# Adafruit_MacroPad_2040_rev_D.net
KiCad netlist of a schematic drawn in EAGLE
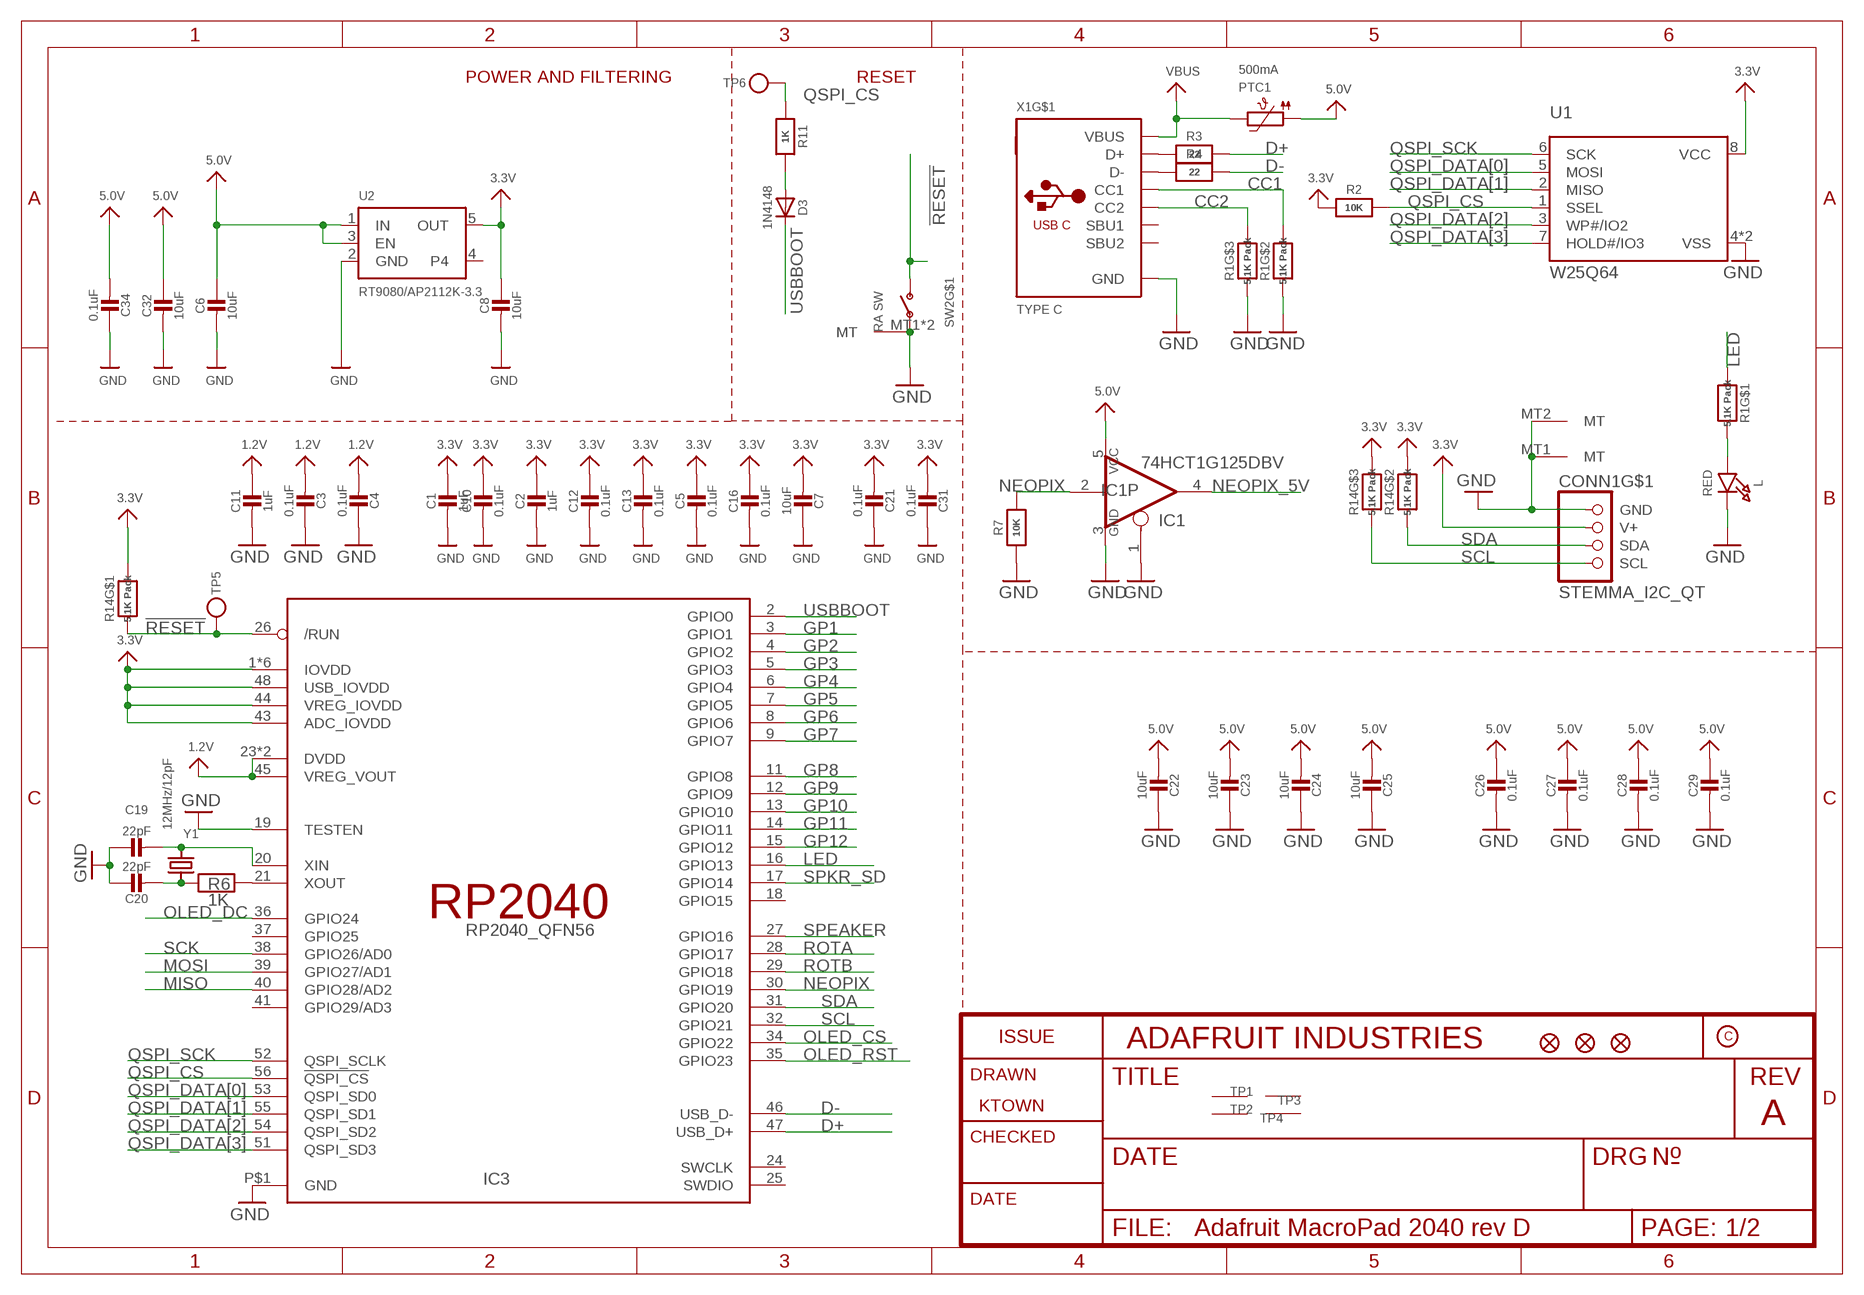
[diagram p0: schematic, sheet 1]
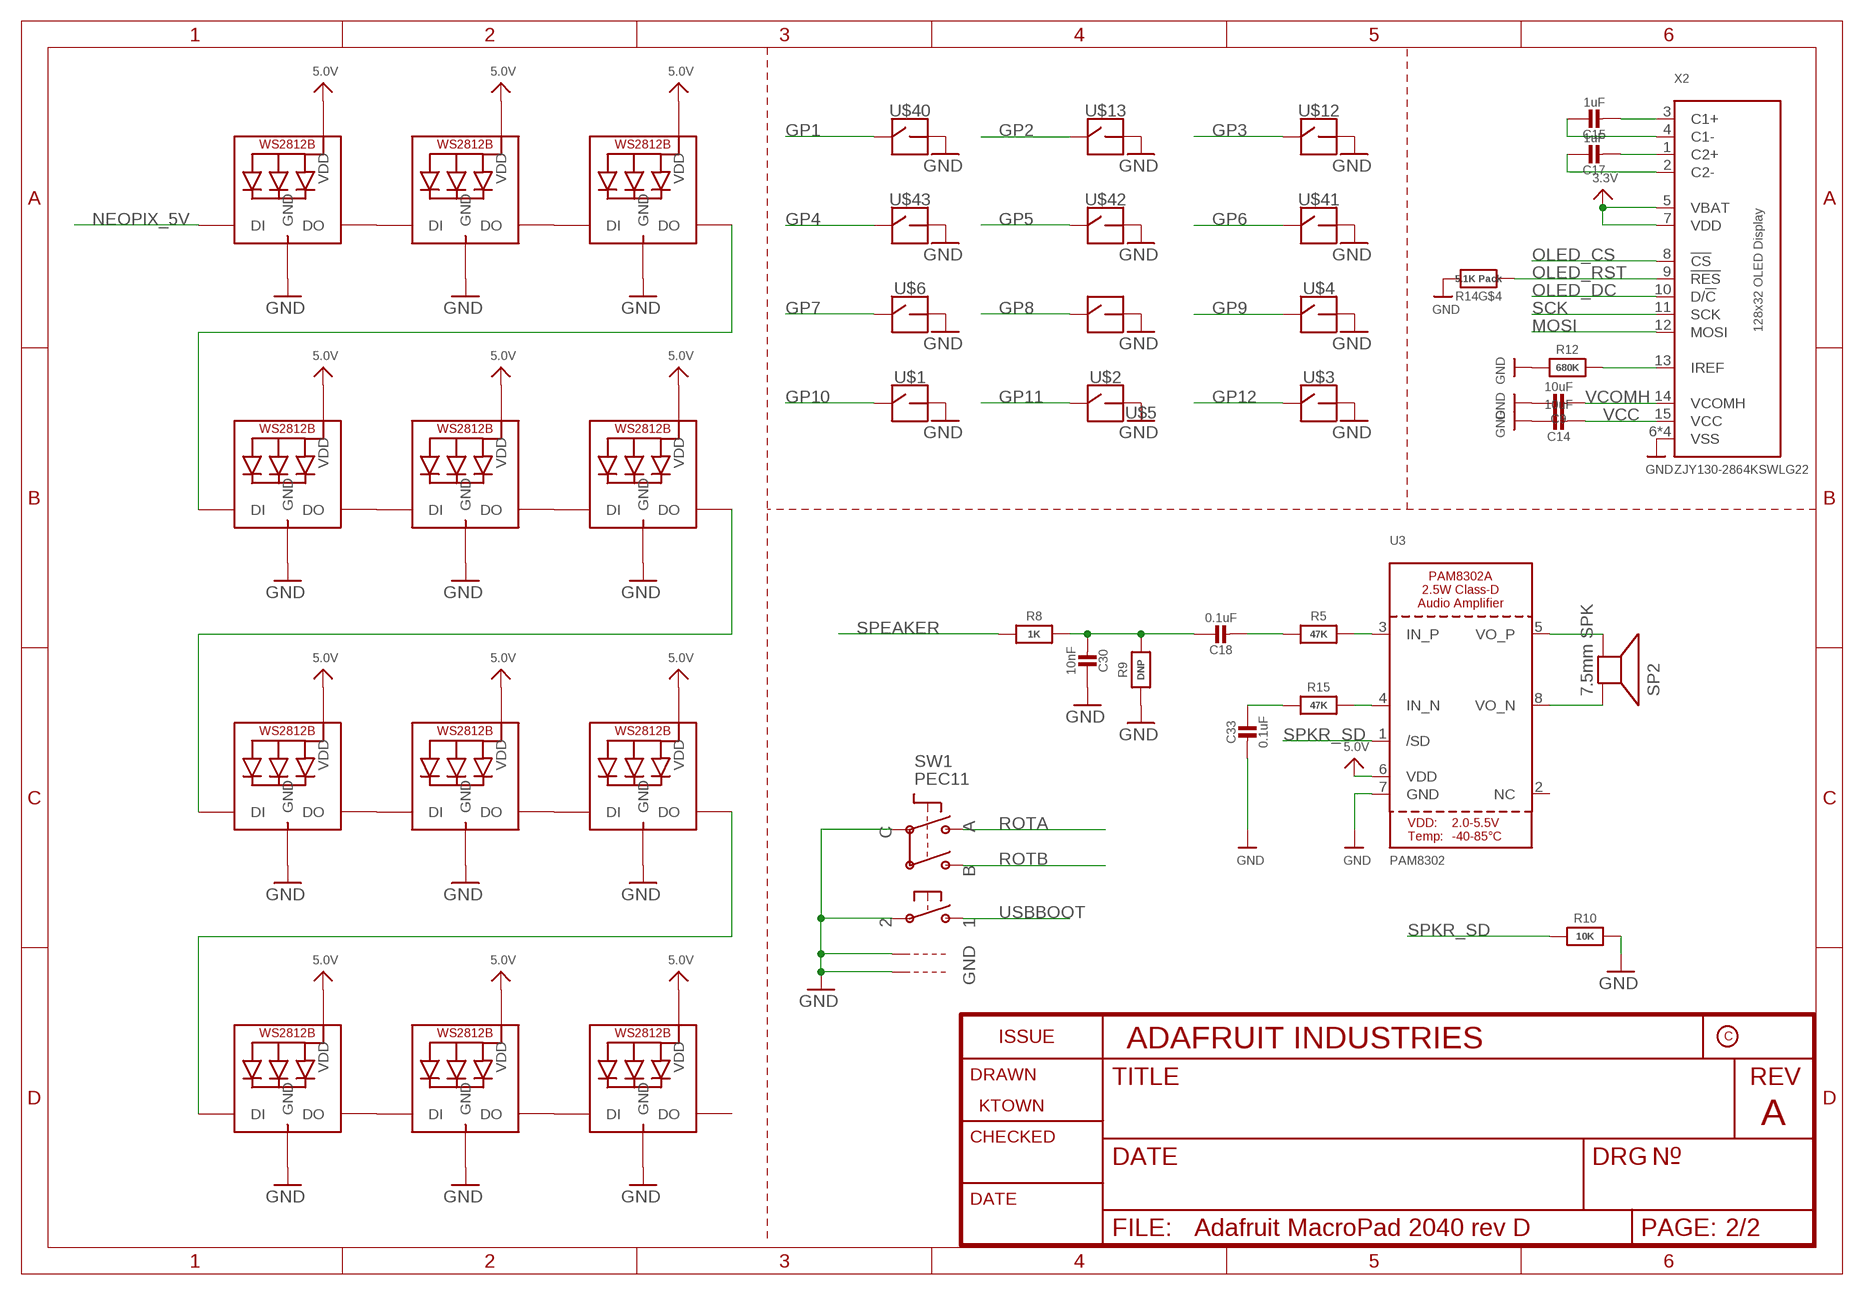
[diagram p1: schematic, sheet 2]

(export (version "E")
  (design (tool "Eeschema 10.0.6"))
  (components
    (comp (ref "C1")
      (value "1uF")
      (footprint "eagle-import:0603-NO")
      (libsource (lib "eagle-import") (part "CAP_CERAMIC0603_NO"))
    )
    (comp (ref "C2")
      (value "1uF")
      (footprint "eagle-import:0603-NO")
      (libsource (lib "eagle-import") (part "CAP_CERAMIC0603_NO"))
    )
    (comp (ref "C3")
      (value "0.1uF")
      (footprint "eagle-import:0603-NO")
      (libsource (lib "eagle-import") (part "CAP_CERAMIC0603_NO"))
    )
    (comp (ref "C4")
      (value "0.1uF")
      (footprint "eagle-import:0603-NO")
      (libsource (lib "eagle-import") (part "CAP_CERAMIC0603_NO"))
    )
    (comp (ref "C5")
      (value "0.1uF")
      (footprint "eagle-import:0603-NO")
      (libsource (lib "eagle-import") (part "CAP_CERAMIC0603_NO"))
    )
    (comp (ref "C6")
      (value "10uF")
      (footprint "eagle-import:0805-NO")
      (libsource (lib "eagle-import") (part "CAP_CERAMIC0805-NOOUTLINE"))
    )
    (comp (ref "C7")
      (value "10uF")
      (footprint "eagle-import:0805-NO")
      (libsource (lib "eagle-import") (part "CAP_CERAMIC0805-NOOUTLINE"))
    )
    (comp (ref "C8")
      (value "10uF")
      (footprint "eagle-import:0805-NO")
      (fields (field (name "REV") "D"))
      (libsource (lib "eagle-import") (part "CAP_CERAMIC0805-NOOUTLINE"))
    )
    (comp (ref "C10")
      (value "0.1uF")
      (footprint "eagle-import:0603-NO")
      (libsource (lib "eagle-import") (part "CAP_CERAMIC0603_NO"))
    )
    (comp (ref "C11")
      (value "1uF")
      (footprint "eagle-import:0603-NO")
      (libsource (lib "eagle-import") (part "CAP_CERAMIC0603_NO"))
    )
    (comp (ref "C12")
      (value "0.1uF")
      (footprint "eagle-import:0603-NO")
      (libsource (lib "eagle-import") (part "CAP_CERAMIC0603_NO"))
    )
    (comp (ref "C13")
      (value "0.1uF")
      (footprint "eagle-import:0603-NO")
      (libsource (lib "eagle-import") (part "CAP_CERAMIC0603_NO"))
    )
    (comp (ref "C16")
      (value "0.1uF")
      (footprint "eagle-import:0603-NO")
      (libsource (lib "eagle-import") (part "CAP_CERAMIC0603_NO"))
    )
    (comp (ref "C19")
      (value "22pF")
      (footprint "eagle-import:0603-NO")
      (libsource (lib "eagle-import") (part "CAP_CERAMIC0603_NO"))
    )
    (comp (ref "C20")
      (value "22pF")
      (footprint "eagle-import:0603-NO")
      (libsource (lib "eagle-import") (part "CAP_CERAMIC0603_NO"))
    )
    (comp (ref "C21")
      (value "0.1uF")
      (footprint "eagle-import:0603-NO")
      (libsource (lib "eagle-import") (part "CAP_CERAMIC0603_NO"))
    )
    (comp (ref "C22")
      (value "10uF")
      (footprint "eagle-import:0805-NO")
      (libsource (lib "eagle-import") (part "CAP_CERAMIC0805-NOOUTLINE"))
    )
    (comp (ref "C23")
      (value "10uF")
      (footprint "eagle-import:0805-NO")
      (libsource (lib "eagle-import") (part "CAP_CERAMIC0805-NOOUTLINE"))
    )
    (comp (ref "C24")
      (value "10uF")
      (footprint "eagle-import:0805-NO")
      (libsource (lib "eagle-import") (part "CAP_CERAMIC0805-NOOUTLINE"))
    )
    (comp (ref "C25")
      (value "10uF")
      (footprint "eagle-import:0805-NO")
      (libsource (lib "eagle-import") (part "CAP_CERAMIC0805-NOOUTLINE"))
    )
    (comp (ref "C26")
      (value "0.1uF")
      (footprint "eagle-import:0603-NO")
      (libsource (lib "eagle-import") (part "CAP_CERAMIC0603_NO"))
    )
    (comp (ref "C27")
      (value "0.1uF")
      (footprint "eagle-import:0603-NO")
      (libsource (lib "eagle-import") (part "CAP_CERAMIC0603_NO"))
    )
    (comp (ref "C28")
      (value "0.1uF")
      (footprint "eagle-import:0603-NO")
      (libsource (lib "eagle-import") (part "CAP_CERAMIC0603_NO"))
    )
    (comp (ref "C29")
      (value "0.1uF")
      (footprint "eagle-import:0603-NO")
      (libsource (lib "eagle-import") (part "CAP_CERAMIC0603_NO"))
    )
    (comp (ref "C31")
      (value "0.1uF")
      (footprint "eagle-import:0603-NO")
      (libsource (lib "eagle-import") (part "CAP_CERAMIC0603_NO"))
    )
    (comp (ref "C32")
      (value "10uF")
      (footprint "eagle-import:0805-NO")
      (libsource (lib "eagle-import") (part "CAP_CERAMIC0805-NOOUTLINE"))
    )
    (comp (ref "C34")
      (value "0.1uF")
      (footprint "eagle-import:0603-NO")
      (libsource (lib "eagle-import") (part "CAP_CERAMIC0603_NO"))
    )
    (comp (ref "CONN1")
      (value "STEMMA_I2C_QT")
      (footprint "eagle-import:JST_SH4")
      (libsource (lib "eagle-import") (part "STEMMA_I2C_QT"))
    )
    (comp (ref "D3")
      (value "1N4148")
      (footprint "eagle-import:SOD-323")
      (libsource (lib "eagle-import") (part "DIODESOD-323"))
    )
    (comp (ref "IC1")
      (value "74HCT1G125DBV")
      (footprint "eagle-import:SOT23-5")
      (libsource (lib "eagle-import") (part "741G125DBVAHC"))
    )
    (comp (ref "IC3")
      (value "RP2040_QFN56")
      (footprint "eagle-import:QFN56_7MM_REDUCEDEPAD")
      (libsource (lib "eagle-import") (part "RP2040_QFN56"))
    )
    (comp (ref "L")
      (value "RED")
      (footprint "eagle-import:CHIPLED_0603_NOOUTLINE")
      (libsource (lib "eagle-import") (part "LED0603_NOOUTLINE"))
    )
    (comp (ref "PTC1")
      (value "500mA")
      (footprint "eagle-import:0805-NO")
      (libsource (lib "eagle-import") (part "PTC_0805"))
    )
    (comp (ref "R1")
      (value "5.1K Pack")
      (footprint "eagle-import:RESPACK_4X0603")
      (libsource (lib "eagle-import") (part "RESISTOR_4PACK"))
    )
    (comp (ref "R2")
      (value "10K")
      (footprint "eagle-import:0603-NO")
      (libsource (lib "eagle-import") (part "RESISTOR_0603_NOOUT"))
    )
    (comp (ref "R3")
      (value "22")
      (footprint "eagle-import:0603-NO")
      (libsource (lib "eagle-import") (part "RESISTOR_0603_NOOUT"))
    )
    (comp (ref "R4")
      (value "22")
      (footprint "eagle-import:0603-NO")
      (libsource (lib "eagle-import") (part "RESISTOR_0603_NOOUT"))
    )
    (comp (ref "R6")
      (value "1K")
      (footprint "eagle-import:0603-NO")
      (libsource (lib "eagle-import") (part "RESISTOR_0603_NOOUT"))
    )
    (comp (ref "R7")
      (value "10K")
      (footprint "eagle-import:0603-NO")
      (libsource (lib "eagle-import") (part "RESISTOR_0603_NOOUT"))
    )
    (comp (ref "R11")
      (value "1K")
      (footprint "eagle-import:0603-NO")
      (libsource (lib "eagle-import") (part "RESISTOR_0603_NOOUT"))
    )
    (comp (ref "R14")
      (value "5.1K Pack")
      (footprint "eagle-import:RESPACK_4X0603")
      (libsource (lib "eagle-import") (part "RESISTOR_4PACK"))
    )
    (comp (ref "SW2")
      (value "RA SW")
      (footprint "eagle-import:SPST_TACTILE_RA")
      (libsource (lib "eagle-import") (part "SWITCH_SPST_MNT_TACT_RA"))
    )
    (comp (ref "TP1")
      (value "SEWTAP_SMTNUTM3")
      (footprint "eagle-import:SMT_NUT_3MM")
      (libsource (lib "eagle-import") (part "SEWTAP_SMTNUTM3"))
    )
    (comp (ref "TP2")
      (value "SEWTAP_SMTNUTM3")
      (footprint "eagle-import:SMT_NUT_3MM")
      (libsource (lib "eagle-import") (part "SEWTAP_SMTNUTM3"))
    )
    (comp (ref "TP3")
      (value "SEWTAP_SMTNUTM3")
      (footprint "eagle-import:SMT_NUT_3MM")
      (libsource (lib "eagle-import") (part "SEWTAP_SMTNUTM3"))
    )
    (comp (ref "TP4")
      (value "SEWTAP_SMTNUTM3")
      (footprint "eagle-import:SMT_NUT_3MM")
      (libsource (lib "eagle-import") (part "SEWTAP_SMTNUTM3"))
    )
    (comp (ref "TP5")
      (value "TESTPOINTROUND1.5MMNO")
      (footprint "eagle-import:TESTPOINT_ROUND_1.5MM_NO")
      (libsource (lib "eagle-import") (part "TESTPOINTROUND1.5MMNO"))
    )
    (comp (ref "TP6")
      (value "TESTPOINTROUND1.5MMNO")
      (footprint "eagle-import:TESTPOINT_ROUND_1.5MM_NO")
      (libsource (lib "eagle-import") (part "TESTPOINTROUND1.5MMNO"))
    )
    (comp (ref "U$34")
      (value "FIDUCIAL_1MM")
      (footprint "eagle-import:FIDUCIAL_1MM")
      (libsource (lib "eagle-import") (part "FIDUCIAL_1MM"))
    )
    (comp (ref "U$35")
      (value "FIDUCIAL_1MM")
      (footprint "eagle-import:FIDUCIAL_1MM")
      (libsource (lib "eagle-import") (part "FIDUCIAL_1MM"))
    )
    (comp (ref "U$80")
      (value "FIDUCIAL_1MM")
      (footprint "eagle-import:FIDUCIAL_1MM")
      (libsource (lib "eagle-import") (part "FIDUCIAL_1MM"))
    )
    (comp (ref "U1")
      (value "W25Q64")
      (footprint "eagle-import:USON8_4X4")
      (libsource (lib "eagle-import") (part "SPIFLASH_8PIN_4X4"))
    )
    (comp (ref "U2")
      (value "RT9080/AP2112K-3.3")
      (footprint "eagle-import:SOT23-5")
      (fields (field (name "JLC_ROTATION") "0"))
      (libsource (lib "eagle-import") (part "VREG_SOT23-5"))
    )
    (comp (ref "X1")
      (value "TYPE C")
      (footprint "eagle-import:USB_C_CUSB31-CFM2AX-01-X")
      (libsource (lib "eagle-import") (part "USB_C"))
    )
    (comp (ref "Y1")
      (value "12MHz/12pF")
      (footprint "eagle-import:CRYSTAL_2.5X2")
      (libsource (lib "eagle-import") (part "CRYSTAL2.5X2.0"))
    )
    (comp (ref "C9")
      (value "10uF")
      (footprint "eagle-import:0805-NO")
      (libsource (lib "eagle-import") (part "CAP_CERAMIC0805-NOOUTLINE"))
    )
    (comp (ref "C14")
      (value "10uF")
      (footprint "eagle-import:0805-NO")
      (libsource (lib "eagle-import") (part "CAP_CERAMIC0805-NOOUTLINE"))
    )
    (comp (ref "C15")
      (value "1uF")
      (footprint "eagle-import:0603-NO")
      (libsource (lib "eagle-import") (part "CAP_CERAMIC0603_NO"))
    )
    (comp (ref "C17")
      (value "1uF")
      (footprint "eagle-import:0603-NO")
      (libsource (lib "eagle-import") (part "CAP_CERAMIC0603_NO"))
    )
    (comp (ref "C18")
      (value "0.1uF")
      (footprint "eagle-import:0603-NO")
      (libsource (lib "eagle-import") (part "CAP_CERAMIC0603_NO"))
    )
    (comp (ref "C30")
      (value "10nF")
      (footprint "eagle-import:0603-NO")
      (libsource (lib "eagle-import") (part "CAP_CERAMIC0603_NO"))
    )
    (comp (ref "C33")
      (value "0.1uF")
      (footprint "eagle-import:0603-NO")
      (libsource (lib "eagle-import") (part "CAP_CERAMIC0603_NO"))
    )
    (comp (ref "LED1")
      (value "WS2812B_SK6812E")
      (footprint "eagle-import:NEO3535_REVERSE")
      (libsource (lib "eagle-import") (part "WS2812B_SK6812E"))
    )
    (comp (ref "LED2")
      (value "WS2812B_SK6812E")
      (footprint "eagle-import:NEO3535_REVERSE")
      (libsource (lib "eagle-import") (part "WS2812B_SK6812E"))
    )
    (comp (ref "LED3")
      (value "WS2812B_SK6812E")
      (footprint "eagle-import:NEO3535_REVERSE")
      (libsource (lib "eagle-import") (part "WS2812B_SK6812E"))
    )
    (comp (ref "LED4")
      (value "WS2812B_SK6812E")
      (footprint "eagle-import:NEO3535_REVERSE")
      (libsource (lib "eagle-import") (part "WS2812B_SK6812E"))
    )
    (comp (ref "LED5")
      (value "WS2812B_SK6812E")
      (footprint "eagle-import:NEO3535_REVERSE")
      (libsource (lib "eagle-import") (part "WS2812B_SK6812E"))
    )
    (comp (ref "LED6")
      (value "WS2812B_SK6812E")
      (footprint "eagle-import:NEO3535_REVERSE")
      (libsource (lib "eagle-import") (part "WS2812B_SK6812E"))
    )
    (comp (ref "LED7")
      (value "WS2812B_SK6812E")
      (footprint "eagle-import:NEO3535_REVERSE")
      (libsource (lib "eagle-import") (part "WS2812B_SK6812E"))
    )
    (comp (ref "LED8")
      (value "WS2812B_SK6812E")
      (footprint "eagle-import:NEO3535_REVERSE")
      (libsource (lib "eagle-import") (part "WS2812B_SK6812E"))
    )
    (comp (ref "LED9")
      (value "WS2812B_SK6812E")
      (footprint "eagle-import:NEO3535_REVERSE")
      (libsource (lib "eagle-import") (part "WS2812B_SK6812E"))
    )
    (comp (ref "LED10")
      (value "WS2812B_SK6812E")
      (footprint "eagle-import:NEO3535_REVERSE")
      (libsource (lib "eagle-import") (part "WS2812B_SK6812E"))
    )
    (comp (ref "LED11")
      (value "WS2812B_SK6812E")
      (footprint "eagle-import:NEO3535_REVERSE")
      (libsource (lib "eagle-import") (part "WS2812B_SK6812E"))
    )
    (comp (ref "LED12")
      (value "WS2812B_SK6812E")
      (footprint "eagle-import:NEO3535_REVERSE")
      (libsource (lib "eagle-import") (part "WS2812B_SK6812E"))
    )
    (comp (ref "R5")
      (value "47K")
      (footprint "eagle-import:0603-NO")
      (libsource (lib "eagle-import") (part "RESISTOR_0603_NOOUT"))
    )
    (comp (ref "R8")
      (value "1K")
      (footprint "eagle-import:0603-NO")
      (libsource (lib "eagle-import") (part "RESISTOR_0603_NOOUT"))
    )
    (comp (ref "R9")
      (value "DNP")
      (footprint "eagle-import:0603-NO")
      (libsource (lib "eagle-import") (part "RESISTOR_0603_NOOUT"))
    )
    (comp (ref "R10")
      (value "10K")
      (footprint "eagle-import:0603-NO")
      (libsource (lib "eagle-import") (part "RESISTOR_0603_NOOUT"))
    )
    (comp (ref "R12")
      (value "680K")
      (footprint "eagle-import:0603-NO")
      (libsource (lib "eagle-import") (part "RESISTOR_0603_NOOUT"))
    )
    (comp (ref "R15")
      (value "47K")
      (footprint "eagle-import:0603-NO")
      (libsource (lib "eagle-import") (part "RESISTOR_0603_NOOUT"))
    )
    (comp (ref "SP2")
      (value "7.5mm SPK")
      (footprint "eagle-import:BUZZER_SMT_7.5MM")
      (fields (field (name "ROT") "0"))
      (libsource (lib "eagle-import") (part "SPEAKER_7.5MM"))
    )
    (comp (ref "SW1")
      (value "PEC11")
      (footprint "eagle-import:PEC11_SW_FIXED")
      (libsource (lib "eagle-import") (part "ENCODER_PLUS_SWITCH_EC11_DFM"))
    )
    (comp (ref "U$1")
      (value "SOCKET")
      (footprint "eagle-import:KAILH_SOCKET")
      (fields (field (name "XOFFSET") "-.5"))
      (libsource (lib "eagle-import") (part "KBD_SWITCH_KAILH_SOCKETBOX_JADE_KAILH_SOCKET"))
    )
    (comp (ref "U$2")
      (value "SOCKET")
      (footprint "eagle-import:KAILH_SOCKET")
      (fields (field (name "XOFFSET") "-.5"))
      (libsource (lib "eagle-import") (part "KBD_SWITCH_KAILH_SOCKETBOX_JADE_KAILH_SOCKET"))
    )
    (comp (ref "U$3")
      (value "SOCKET")
      (footprint "eagle-import:KAILH_SOCKET")
      (fields (field (name "XOFFSET") "-.5"))
      (libsource (lib "eagle-import") (part "KBD_SWITCH_KAILH_SOCKETBOX_JADE_KAILH_SOCKET"))
    )
    (comp (ref "U$4")
      (value "SOCKET")
      (footprint "eagle-import:KAILH_SOCKET")
      (fields (field (name "XOFFSET") "-.5"))
      (libsource (lib "eagle-import") (part "KBD_SWITCH_KAILH_SOCKETBOX_JADE_KAILH_SOCKET"))
    )
    (comp (ref "U$5")
      (value "SOCKET")
      (footprint "eagle-import:KAILH_SOCKET")
      (fields (field (name "XOFFSET") "-.5"))
      (libsource (lib "eagle-import") (part "KBD_SWITCH_KAILH_SOCKETBOX_JADE_KAILH_SOCKET"))
    )
    (comp (ref "U$6")
      (value "SOCKET")
      (footprint "eagle-import:KAILH_SOCKET")
      (fields (field (name "XOFFSET") "-.5"))
      (libsource (lib "eagle-import") (part "KBD_SWITCH_KAILH_SOCKETBOX_JADE_KAILH_SOCKET"))
    )
    (comp (ref "U$12")
      (value "SOCKET")
      (footprint "eagle-import:KAILH_SOCKET")
      (fields (field (name "XOFFSET") "-.5"))
      (libsource (lib "eagle-import") (part "KBD_SWITCH_KAILH_SOCKETBOX_JADE_KAILH_SOCKET"))
    )
    (comp (ref "U$13")
      (value "SOCKET")
      (footprint "eagle-import:KAILH_SOCKET")
      (fields (field (name "XOFFSET") "-.5"))
      (libsource (lib "eagle-import") (part "KBD_SWITCH_KAILH_SOCKETBOX_JADE_KAILH_SOCKET"))
    )
    (comp (ref "U$40")
      (value "SOCKET")
      (footprint "eagle-import:KAILH_SOCKET")
      (fields (field (name "XOFFSET") "-.5"))
      (libsource (lib "eagle-import") (part "KBD_SWITCH_KAILH_SOCKETBOX_JADE_KAILH_SOCKET"))
    )
    (comp (ref "U$41")
      (value "SOCKET")
      (footprint "eagle-import:KAILH_SOCKET")
      (fields (field (name "XOFFSET") "-.5"))
      (libsource (lib "eagle-import") (part "KBD_SWITCH_KAILH_SOCKETBOX_JADE_KAILH_SOCKET"))
    )
    (comp (ref "U$42")
      (value "SOCKET")
      (footprint "eagle-import:KAILH_SOCKET")
      (fields (field (name "XOFFSET") "-.5"))
      (libsource (lib "eagle-import") (part "KBD_SWITCH_KAILH_SOCKETBOX_JADE_KAILH_SOCKET"))
    )
    (comp (ref "U$43")
      (value "SOCKET")
      (footprint "eagle-import:KAILH_SOCKET")
      (fields (field (name "XOFFSET") "-.5"))
      (libsource (lib "eagle-import") (part "KBD_SWITCH_KAILH_SOCKETBOX_JADE_KAILH_SOCKET"))
    )
    (comp (ref "U3")
      (value "PAM8302")
      (footprint "eagle-import:MSOP8_0.65MM")
      (libsource (lib "eagle-import") (part "AUDIOAMP_PAM8302A"))
    )
    (comp (ref "X2")
      (value "ZJY130-2864KSWLG22")
      (footprint "eagle-import:ZJY130-2864KSWLG22")
      (libsource (lib "eagle-import") (part "ZJY130-2864KSWLG22"))
    )
  )
  (nets
    (net (code "1") (name "1.2V") (class "Default")
      (node (ref "C11") (pin "1") (pinfunction "1_1") (pintype "passive"))
      (node (ref "C3") (pin "2") (pinfunction "2_2") (pintype "passive"))
      (node (ref "C4") (pin "2") (pinfunction "2_2") (pintype "passive"))
      (node (ref "IC3") (pin "23") (pinfunction "DVDD_23") (pintype "power_in"))
      (node (ref "IC3") (pin "45") (pinfunction "VREG_VOUT_45") (pintype "power_in"))
      (node (ref "IC3") (pin "50") (pinfunction "DVDD_50") (pintype "power_in"))
    )
    (net (code "2") (name "3.3V") (class "Default")
      (node (ref "C1") (pin "1") (pinfunction "1_1") (pintype "passive"))
      (node (ref "C10") (pin "1") (pinfunction "1_1") (pintype "passive"))
      (node (ref "C12") (pin "1") (pinfunction "1_1") (pintype "passive"))
      (node (ref "C13") (pin "1") (pinfunction "1_1") (pintype "passive"))
      (node (ref "C16") (pin "1") (pinfunction "1_1") (pintype "passive"))
      (node (ref "C2") (pin "1") (pinfunction "1_1") (pintype "passive"))
      (node (ref "C21") (pin "2") (pinfunction "2_2") (pintype "passive"))
      (node (ref "C31") (pin "2") (pinfunction "2_2") (pintype "passive"))
      (node (ref "C5") (pin "1") (pinfunction "1_1") (pintype "passive"))
      (node (ref "C7") (pin "2") (pinfunction "2_2") (pintype "passive"))
      (node (ref "C8") (pin "1") (pinfunction "1_1") (pintype "passive"))
      (node (ref "CONN1") (pin "2") (pinfunction "V+_2") (pintype "passive"))
      (node (ref "IC3") (pin "1") (pinfunction "IOVDD_1") (pintype "power_in"))
      (node (ref "IC3") (pin "10") (pinfunction "IOVDD_10") (pintype "power_in"))
      (node (ref "IC3") (pin "22") (pinfunction "IOVDD_22") (pintype "power_in"))
      (node (ref "IC3") (pin "33") (pinfunction "IOVDD_33") (pintype "power_in"))
      (node (ref "IC3") (pin "42") (pinfunction "IOVDD_42") (pintype "power_in"))
      (node (ref "IC3") (pin "43") (pinfunction "ADC_IOVDD_43") (pintype "power_in"))
      (node (ref "IC3") (pin "44") (pinfunction "VREG_IOVDD_44") (pintype "power_in"))
      (node (ref "IC3") (pin "48") (pinfunction "USB_IOVDD_48") (pintype "power_in"))
      (node (ref "IC3") (pin "49") (pinfunction "IOVDD_49") (pintype "power_in"))
      (node (ref "R14") (pin "6") (pinfunction "2_6") (pintype "passive"))
      (node (ref "R14") (pin "7") (pinfunction "2_7") (pintype "passive"))
      (node (ref "R14") (pin "8") (pinfunction "2_8") (pintype "passive"))
      (node (ref "R2") (pin "1") (pinfunction "1_1") (pintype "passive"))
      (node (ref "U1") (pin "8") (pinfunction "VCC_8") (pintype "bidirectional"))
      (node (ref "U2") (pin "5") (pinfunction "OUT_5") (pintype "power_in"))
      (node (ref "X2") (pin "5") (pinfunction "VBAT_5") (pintype "power_in"))
      (node (ref "X2") (pin "7") (pinfunction "VDD_7") (pintype "power_in"))
    )
    (net (code "3") (name "5.0V") (class "Default")
      (node (ref "C22") (pin "2") (pinfunction "2_2") (pintype "passive"))
      (node (ref "C23") (pin "2") (pinfunction "2_2") (pintype "passive"))
      (node (ref "C24") (pin "2") (pinfunction "2_2") (pintype "passive"))
      (node (ref "C25") (pin "2") (pinfunction "2_2") (pintype "passive"))
      (node (ref "C26") (pin "1") (pinfunction "1_1") (pintype "passive"))
      (node (ref "C27") (pin "1") (pinfunction "1_1") (pintype "passive"))
      (node (ref "C28") (pin "1") (pinfunction "1_1") (pintype "passive"))
      (node (ref "C29") (pin "1") (pinfunction "1_1") (pintype "passive"))
      (node (ref "C32") (pin "1") (pinfunction "1_1") (pintype "passive"))
      (node (ref "C34") (pin "2") (pinfunction "2_2") (pintype "passive"))
      (node (ref "C6") (pin "1") (pinfunction "1_1") (pintype "passive"))
      (node (ref "IC1") (pin "5") (pinfunction "VCC_5") (pintype "power_in"))
      (node (ref "LED1") (pin "1-VDD") (pinfunction "VDD_1-VDD") (pintype "power_in"))
      (node (ref "LED10") (pin "1-VDD") (pinfunction "VDD_1-VDD") (pintype "power_in"))
      (node (ref "LED11") (pin "1-VDD") (pinfunction "VDD_1-VDD") (pintype "power_in"))
      (node (ref "LED12") (pin "1-VDD") (pinfunction "VDD_1-VDD") (pintype "power_in"))
      (node (ref "LED2") (pin "1-VDD") (pinfunction "VDD_1-VDD") (pintype "power_in"))
      (node (ref "LED3") (pin "1-VDD") (pinfunction "VDD_1-VDD") (pintype "power_in"))
      (node (ref "LED4") (pin "1-VDD") (pinfunction "VDD_1-VDD") (pintype "power_in"))
      (node (ref "LED5") (pin "1-VDD") (pinfunction "VDD_1-VDD") (pintype "power_in"))
      (node (ref "LED6") (pin "1-VDD") (pinfunction "VDD_1-VDD") (pintype "power_in"))
      (node (ref "LED7") (pin "1-VDD") (pinfunction "VDD_1-VDD") (pintype "power_in"))
      (node (ref "LED8") (pin "1-VDD") (pinfunction "VDD_1-VDD") (pintype "power_in"))
      (node (ref "LED9") (pin "1-VDD") (pinfunction "VDD_1-VDD") (pintype "power_in"))
      (node (ref "PTC1") (pin "1") (pinfunction "1_1") (pintype "passive"))
      (node (ref "U2") (pin "1") (pinfunction "IN_1") (pintype "power_in"))
      (node (ref "U2") (pin "3") (pinfunction "EN_3") (pintype "input"))
      (node (ref "U3") (pin "6") (pinfunction "VDD_6") (pintype "power_in"))
    )
    (net (code "4") (name "CC1") (class "Default")
      (node (ref "R1") (pin "7") (pinfunction "2_7") (pintype "passive"))
      (node (ref "X1") (pin "A5") (pinfunction "CC1_A5") (pintype "bidirectional"))
    )
    (net (code "5") (name "CC2") (class "Default")
      (node (ref "R1") (pin "6") (pinfunction "2_6") (pintype "passive"))
      (node (ref "X1") (pin "B5") (pinfunction "CC2_B5") (pintype "bidirectional"))
    )
    (net (code "6") (name "D+") (class "Default")
      (node (ref "IC3") (pin "47") (pinfunction "USB_D+_47") (pintype "bidirectional"))
      (node (ref "R3") (pin "2") (pinfunction "2_2") (pintype "passive"))
    )
    (net (code "7") (name "D-") (class "Default")
      (node (ref "IC3") (pin "46") (pinfunction "USB_D-_46") (pintype "bidirectional"))
      (node (ref "R4") (pin "2") (pinfunction "2_2") (pintype "passive"))
    )
    (net (code "8") (name "GND") (class "Default")
      (node (ref "C1") (pin "2") (pinfunction "2_2") (pintype "passive"))
      (node (ref "C10") (pin "2") (pinfunction "2_2") (pintype "passive"))
      (node (ref "C11") (pin "2") (pinfunction "2_2") (pintype "passive"))
      (node (ref "C12") (pin "2") (pinfunction "2_2") (pintype "passive"))
      (node (ref "C13") (pin "2") (pinfunction "2_2") (pintype "passive"))
      (node (ref "C14") (pin "1") (pinfunction "1_1") (pintype "passive"))
      (node (ref "C16") (pin "2") (pinfunction "2_2") (pintype "passive"))
      (node (ref "C19") (pin "1") (pinfunction "1_1") (pintype "passive"))
      (node (ref "C2") (pin "2") (pinfunction "2_2") (pintype "passive"))
      (node (ref "C20") (pin "1") (pinfunction "1_1") (pintype "passive"))
      (node (ref "C21") (pin "1") (pinfunction "1_1") (pintype "passive"))
      (node (ref "C22") (pin "1") (pinfunction "1_1") (pintype "passive"))
      (node (ref "C23") (pin "1") (pinfunction "1_1") (pintype "passive"))
      (node (ref "C24") (pin "1") (pinfunction "1_1") (pintype "passive"))
      (node (ref "C25") (pin "1") (pinfunction "1_1") (pintype "passive"))
      (node (ref "C26") (pin "2") (pinfunction "2_2") (pintype "passive"))
      (node (ref "C27") (pin "2") (pinfunction "2_2") (pintype "passive"))
      (node (ref "C28") (pin "2") (pinfunction "2_2") (pintype "passive"))
      (node (ref "C29") (pin "2") (pinfunction "2_2") (pintype "passive"))
      (node (ref "C3") (pin "1") (pinfunction "1_1") (pintype "passive"))
      (node (ref "C30") (pin "1") (pinfunction "1_1") (pintype "passive"))
      (node (ref "C31") (pin "1") (pinfunction "1_1") (pintype "passive"))
      (node (ref "C32") (pin "2") (pinfunction "2_2") (pintype "passive"))
      (node (ref "C33") (pin "2") (pinfunction "2_2") (pintype "passive"))
      (node (ref "C34") (pin "1") (pinfunction "1_1") (pintype "passive"))
      (node (ref "C4") (pin "1") (pinfunction "1_1") (pintype "passive"))
      (node (ref "C5") (pin "2") (pinfunction "2_2") (pintype "passive"))
      (node (ref "C6") (pin "2") (pinfunction "2_2") (pintype "passive"))
      (node (ref "C7") (pin "1") (pinfunction "1_1") (pintype "passive"))
      (node (ref "C8") (pin "2") (pinfunction "2_2") (pintype "passive"))
      (node (ref "C9") (pin "1") (pinfunction "1_1") (pintype "passive"))
      (node (ref "CONN1") (pin "1") (pinfunction "GND_1") (pintype "passive"))
      (node (ref "CONN1") (pin "MT1") (pinfunction "MT_MT1") (pintype "bidirectional"))
      (node (ref "CONN1") (pin "MT2") (pinfunction "MT_MT2") (pintype "bidirectional"))
      (node (ref "IC1") (pin "1") (pinfunction "OE_1") (pintype "input"))
      (node (ref "IC1") (pin "3") (pinfunction "GND_3") (pintype "power_in"))
      (node (ref "IC3") (pin "19") (pinfunction "TESTEN_19") (pintype "input"))
      (node (ref "IC3") (pin "P$1") (pinfunction "GND_P$1") (pintype "power_in"))
      (node (ref "L") (pin "C") (pinfunction "C_C") (pintype "passive"))
      (node (ref "LED1") (pin "3-GND") (pinfunction "GND_3-GND") (pintype "power_in"))
      (node (ref "LED10") (pin "3-GND") (pinfunction "GND_3-GND") (pintype "power_in"))
      (node (ref "LED11") (pin "3-GND") (pinfunction "GND_3-GND") (pintype "power_in"))
      (node (ref "LED12") (pin "3-GND") (pinfunction "GND_3-GND") (pintype "power_in"))
      (node (ref "LED2") (pin "3-GND") (pinfunction "GND_3-GND") (pintype "power_in"))
      (node (ref "LED3") (pin "3-GND") (pinfunction "GND_3-GND") (pintype "power_in"))
      (node (ref "LED4") (pin "3-GND") (pinfunction "GND_3-GND") (pintype "power_in"))
      (node (ref "LED5") (pin "3-GND") (pinfunction "GND_3-GND") (pintype "power_in"))
      (node (ref "LED6") (pin "3-GND") (pinfunction "GND_3-GND") (pintype "power_in"))
      (node (ref "LED7") (pin "3-GND") (pinfunction "GND_3-GND") (pintype "power_in"))
      (node (ref "LED8") (pin "3-GND") (pinfunction "GND_3-GND") (pintype "power_in"))
      (node (ref "LED9") (pin "3-GND") (pinfunction "GND_3-GND") (pintype "power_in"))
      (node (ref "R1") (pin "2") (pinfunction "1_2") (pintype "passive"))
      (node (ref "R1") (pin "3") (pinfunction "1_3") (pintype "passive"))
      (node (ref "R10") (pin "2") (pinfunction "2_2") (pintype "passive"))
      (node (ref "R12") (pin "1") (pinfunction "1_1") (pintype "passive"))
      (node (ref "R14") (pin "5") (pinfunction "2_5") (pintype "passive"))
      (node (ref "R7") (pin "1") (pinfunction "1_1") (pintype "passive"))
      (node (ref "R9") (pin "1") (pinfunction "1_1") (pintype "passive"))
      (node (ref "SW1") (pin "P$2") (pinfunction "P$2_P$2") (pintype "passive"))
      (node (ref "SW1") (pin "P$C") (pinfunction "P$C_P$C") (pintype "passive"))
      (node (ref "SW1") (pin "P$GND1") (pinfunction "P$GND1_P$GND1") (pintype "passive"))
      (node (ref "SW1") (pin "P$GND2") (pinfunction "P$GND2_P$GND2") (pintype "passive"))
      (node (ref "SW2") (pin "1") (pinfunction "P_1") (pintype "passive"))
      (node (ref "SW2") (pin "MT1") (pinfunction "MT_MT1") (pintype "bidirectional"))
      (node (ref "SW2") (pin "MT2") (pinfunction "MT_MT2") (pintype "bidirectional"))
      (node (ref "U$1") (pin "2") (pinfunction "2_2") (pintype "passive"))
      (node (ref "U$12") (pin "2") (pinfunction "2_2") (pintype "passive"))
      (node (ref "U$13") (pin "2") (pinfunction "2_2") (pintype "passive"))
      (node (ref "U$2") (pin "2") (pinfunction "2_2") (pintype "passive"))
      (node (ref "U$3") (pin "2") (pinfunction "2_2") (pintype "passive"))
      (node (ref "U$4") (pin "2") (pinfunction "2_2") (pintype "passive"))
      (node (ref "U$40") (pin "2") (pinfunction "2_2") (pintype "passive"))
      (node (ref "U$41") (pin "2") (pinfunction "2_2") (pintype "passive"))
      (node (ref "U$42") (pin "2") (pinfunction "2_2") (pintype "passive"))
      (node (ref "U$43") (pin "2") (pinfunction "2_2") (pintype "passive"))
      (node (ref "U$5") (pin "2") (pinfunction "2_2") (pintype "passive"))
      (node (ref "U$6") (pin "2") (pinfunction "2_2") (pintype "passive"))
      (node (ref "U1") (pin "4") (pinfunction "VSS_4") (pintype "bidirectional"))
      (node (ref "U1") (pin "PAD") (pinfunction "VSS_PAD") (pintype "bidirectional"))
      (node (ref "U2") (pin "2") (pinfunction "GND_2") (pintype "power_in"))
      (node (ref "U3") (pin "7") (pinfunction "GND_7") (pintype "power_in"))
      (node (ref "X1") (pin "A1B12") (pinfunction "GND_A1B12") (pintype "power_in"))
      (node (ref "X1") (pin "B1A12") (pinfunction "GND_B1A12") (pintype "power_in"))
      (node (ref "X2") (pin "16") (pinfunction "VSS_16") (pintype "power_in"))
      (node (ref "X2") (pin "6") (pinfunction "VSS_6") (pintype "power_in"))
      (node (ref "X2") (pin "SUPPORT1") (pinfunction "VSS_SUPPORT1") (pintype "power_in"))
      (node (ref "X2") (pin "SUPPORT2") (pinfunction "VSS_SUPPORT2") (pintype "power_in"))
    )
    (net (code "9") (name "GP1") (class "Default")
      (node (ref "IC3") (pin "3") (pinfunction "GPIO1_3") (pintype "bidirectional"))
      (node (ref "U$40") (pin "1") (pinfunction "1_1") (pintype "passive"))
    )
    (net (code "10") (name "GP2") (class "Default")
      (node (ref "IC3") (pin "4") (pinfunction "GPIO2_4") (pintype "bidirectional"))
      (node (ref "U$13") (pin "1") (pinfunction "1_1") (pintype "passive"))
    )
    (net (code "11") (name "GP3") (class "Default")
      (node (ref "IC3") (pin "5") (pinfunction "GPIO3_5") (pintype "bidirectional"))
      (node (ref "U$12") (pin "1") (pinfunction "1_1") (pintype "passive"))
    )
    (net (code "12") (name "GP4") (class "Default")
      (node (ref "IC3") (pin "6") (pinfunction "GPIO4_6") (pintype "bidirectional"))
      (node (ref "U$43") (pin "1") (pinfunction "1_1") (pintype "passive"))
    )
    (net (code "13") (name "GP5") (class "Default")
      (node (ref "IC3") (pin "7") (pinfunction "GPIO5_7") (pintype "bidirectional"))
      (node (ref "U$42") (pin "1") (pinfunction "1_1") (pintype "passive"))
    )
    (net (code "14") (name "GP6") (class "Default")
      (node (ref "IC3") (pin "8") (pinfunction "GPIO6_8") (pintype "bidirectional"))
      (node (ref "U$41") (pin "1") (pinfunction "1_1") (pintype "passive"))
    )
    (net (code "15") (name "GP7") (class "Default")
      (node (ref "IC3") (pin "9") (pinfunction "GPIO7_9") (pintype "bidirectional"))
      (node (ref "U$6") (pin "1") (pinfunction "1_1") (pintype "passive"))
    )
    (net (code "16") (name "GP8") (class "Default")
      (node (ref "IC3") (pin "11") (pinfunction "GPIO8_11") (pintype "bidirectional"))
      (node (ref "U$5") (pin "1") (pinfunction "1_1") (pintype "passive"))
    )
    (net (code "17") (name "GP9") (class "Default")
      (node (ref "IC3") (pin "12") (pinfunction "GPIO9_12") (pintype "bidirectional"))
      (node (ref "U$4") (pin "1") (pinfunction "1_1") (pintype "passive"))
    )
    (net (code "18") (name "GP10") (class "Default")
      (node (ref "IC3") (pin "13") (pinfunction "GPIO10_13") (pintype "bidirectional"))
      (node (ref "U$1") (pin "1") (pinfunction "1_1") (pintype "passive"))
    )
    (net (code "19") (name "GP11") (class "Default")
      (node (ref "IC3") (pin "14") (pinfunction "GPIO11_14") (pintype "bidirectional"))
      (node (ref "U$2") (pin "1") (pinfunction "1_1") (pintype "passive"))
    )
    (net (code "20") (name "GP12") (class "Default")
      (node (ref "IC3") (pin "15") (pinfunction "GPIO12_15") (pintype "bidirectional"))
      (node (ref "U$3") (pin "1") (pinfunction "1_1") (pintype "passive"))
    )
    (net (code "21") (name "LED") (class "Default")
      (node (ref "IC3") (pin "16") (pinfunction "GPIO13_16") (pintype "bidirectional"))
      (node (ref "R1") (pin "1") (pinfunction "1_1") (pintype "passive"))
    )
    (net (code "22") (name "MISO") (class "Default")
      (node (ref "IC3") (pin "40") (pinfunction "GPIO28/AD2_40") (pintype "bidirectional"))
    )
    (net (code "23") (name "MOSI") (class "Default")
      (node (ref "IC3") (pin "39") (pinfunction "GPIO27/AD1_39") (pintype "bidirectional"))
      (node (ref "X2") (pin "12") (pinfunction "MOSI_12") (pintype "input"))
    )
    (net (code "24") (name "NEOPIX") (class "Default")
      (node (ref "IC1") (pin "2") (pinfunction "I_2") (pintype "input"))
      (node (ref "IC3") (pin "30") (pinfunction "GPIO19_30") (pintype "bidirectional"))
      (node (ref "R7") (pin "2") (pinfunction "2_2") (pintype "passive"))
    )
    (net (code "25") (name "NEOPIX_5V") (class "Default")
      (node (ref "IC1") (pin "4") (pinfunction "O_4") (pintype "tri_state"))
      (node (ref "LED1") (pin "4-DIN") (pinfunction "DI_4-DIN") (pintype "input"))
    )
    (net (code "26") (name "Net-(C18-Pad1)") (class "Default")
      (node (ref "C18") (pin "1") (pinfunction "1_1") (pintype "passive"))
      (node (ref "C30") (pin "2") (pinfunction "2_2") (pintype "passive"))
      (node (ref "R8") (pin "2") (pinfunction "2_2") (pintype "passive"))
      (node (ref "R9") (pin "2") (pinfunction "2_2") (pintype "passive"))
    )
    (net (code "27") (name "Net-(C18-Pad2)") (class "Default")
      (node (ref "C18") (pin "2") (pinfunction "2_2") (pintype "passive"))
      (node (ref "R5") (pin "1") (pinfunction "1_1") (pintype "passive"))
    )
    (net (code "28") (name "Net-(C20-Pad2)") (class "Default")
      (node (ref "C20") (pin "2") (pinfunction "2_2") (pintype "passive"))
      (node (ref "R6") (pin "1") (pinfunction "1_1") (pintype "passive"))
      (node (ref "Y1") (pin "1") (pinfunction "1_1") (pintype "passive"))
    )
    (net (code "29") (name "Net-(C33-Pad1)") (class "Default")
      (node (ref "C33") (pin "1") (pinfunction "1_1") (pintype "passive"))
      (node (ref "R15") (pin "1") (pinfunction "1_1") (pintype "passive"))
    )
    (net (code "30") (name "Net-(D3-PadA)") (class "Default")
      (node (ref "D3") (pin "A") (pinfunction "A_A") (pintype "passive"))
      (node (ref "R11") (pin "2") (pinfunction "2_2") (pintype "passive"))
    )
    (net (code "31") (name "Net-(IC3-XIN)") (class "Default")
      (node (ref "C19") (pin "2") (pinfunction "2_2") (pintype "passive"))
      (node (ref "IC3") (pin "20") (pinfunction "XIN_20") (pintype "input"))
      (node (ref "Y1") (pin "3") (pinfunction "2_3") (pintype "passive"))
    )
    (net (code "32") (name "Net-(IC3-XOUT)") (class "Default")
      (node (ref "IC3") (pin "21") (pinfunction "XOUT_21") (pintype "output"))
      (node (ref "R6") (pin "2") (pinfunction "2_2") (pintype "passive"))
    )
    (net (code "33") (name "Net-(LED1-DO)") (class "Default")
      (node (ref "LED1") (pin "2-DOUT") (pinfunction "DO_2-DOUT") (pintype "output"))
      (node (ref "LED2") (pin "4-DIN") (pinfunction "DI_4-DIN") (pintype "input"))
    )
    (net (code "34") (name "Net-(LED2-DO)") (class "Default")
      (node (ref "LED2") (pin "2-DOUT") (pinfunction "DO_2-DOUT") (pintype "output"))
      (node (ref "LED3") (pin "4-DIN") (pinfunction "DI_4-DIN") (pintype "input"))
    )
    (net (code "35") (name "Net-(LED3-DO)") (class "Default")
      (node (ref "LED3") (pin "2-DOUT") (pinfunction "DO_2-DOUT") (pintype "output"))
      (node (ref "LED4") (pin "4-DIN") (pinfunction "DI_4-DIN") (pintype "input"))
    )
    (net (code "36") (name "Net-(LED4-DO)") (class "Default")
      (node (ref "LED4") (pin "2-DOUT") (pinfunction "DO_2-DOUT") (pintype "output"))
      (node (ref "LED5") (pin "4-DIN") (pinfunction "DI_4-DIN") (pintype "input"))
    )
    (net (code "37") (name "Net-(LED5-DO)") (class "Default")
      (node (ref "LED5") (pin "2-DOUT") (pinfunction "DO_2-DOUT") (pintype "output"))
      (node (ref "LED6") (pin "4-DIN") (pinfunction "DI_4-DIN") (pintype "input"))
    )
    (net (code "38") (name "Net-(LED6-DO)") (class "Default")
      (node (ref "LED6") (pin "2-DOUT") (pinfunction "DO_2-DOUT") (pintype "output"))
      (node (ref "LED7") (pin "4-DIN") (pinfunction "DI_4-DIN") (pintype "input"))
    )
    (net (code "39") (name "Net-(LED7-DO)") (class "Default")
      (node (ref "LED7") (pin "2-DOUT") (pinfunction "DO_2-DOUT") (pintype "output"))
      (node (ref "LED8") (pin "4-DIN") (pinfunction "DI_4-DIN") (pintype "input"))
    )
    (net (code "40") (name "Net-(LED8-DO)") (class "Default")
      (node (ref "LED8") (pin "2-DOUT") (pinfunction "DO_2-DOUT") (pintype "output"))
      (node (ref "LED9") (pin "4-DIN") (pinfunction "DI_4-DIN") (pintype "input"))
    )
    (net (code "41") (name "Net-(LED10-DI)") (class "Default")
      (node (ref "LED10") (pin "4-DIN") (pinfunction "DI_4-DIN") (pintype "input"))
      (node (ref "LED9") (pin "2-DOUT") (pinfunction "DO_2-DOUT") (pintype "output"))
    )
    (net (code "42") (name "Net-(LED10-DO)") (class "Default")
      (node (ref "LED10") (pin "2-DOUT") (pinfunction "DO_2-DOUT") (pintype "output"))
      (node (ref "LED11") (pin "4-DIN") (pinfunction "DI_4-DIN") (pintype "input"))
    )
    (net (code "43") (name "Net-(LED11-DO)") (class "Default")
      (node (ref "LED11") (pin "2-DOUT") (pinfunction "DO_2-DOUT") (pintype "output"))
      (node (ref "LED12") (pin "4-DIN") (pinfunction "DI_4-DIN") (pintype "input"))
    )
    (net (code "44") (name "Net-(R1A-2)") (class "Default")
      (node (ref "L") (pin "A") (pinfunction "A_A") (pintype "passive"))
      (node (ref "R1") (pin "8") (pinfunction "2_8") (pintype "passive"))
    )
    (net (code "45") (name "Net-(R3-Pad1)") (class "Default")
      (node (ref "R3") (pin "1") (pinfunction "1_1") (pintype "passive"))
      (node (ref "X1") (pin "A6") (pinfunction "D+_A6") (pintype "bidirectional"))
      (node (ref "X1") (pin "B6") (pinfunction "D+_B6") (pintype "bidirectional"))
    )
    (net (code "46") (name "Net-(R4-Pad1)") (class "Default")
      (node (ref "R4") (pin "1") (pinfunction "1_1") (pintype "passive"))
      (node (ref "X1") (pin "A7") (pinfunction "D-_A7") (pintype "bidirectional"))
      (node (ref "X1") (pin "B7") (pinfunction "D-_B7") (pintype "bidirectional"))
    )
    (net (code "47") (name "Net-(U3-IN_N)") (class "Default")
      (node (ref "R15") (pin "2") (pinfunction "2_2") (pintype "passive"))
      (node (ref "U3") (pin "4") (pinfunction "IN_N_4") (pintype "input"))
    )
    (net (code "48") (name "Net-(U3-IN_P)") (class "Default")
      (node (ref "R5") (pin "2") (pinfunction "2_2") (pintype "passive"))
      (node (ref "U3") (pin "3") (pinfunction "IN_P_3") (pintype "input"))
    )
    (net (code "49") (name "Net-(U3-VO_N)") (class "Default")
      (node (ref "SP2") (pin "+") (pinfunction "+_+") (pintype "passive"))
      (node (ref "U3") (pin "8") (pinfunction "VO_N_8") (pintype "output"))
    )
    (net (code "50") (name "Net-(U3-VO_P)") (class "Default")
      (node (ref "SP2") (pin "-") (pinfunction "-_-") (pintype "passive"))
      (node (ref "U3") (pin "5") (pinfunction "VO_P_5") (pintype "output"))
    )
    (net (code "51") (name "Net-(X2-C1+)") (class "Default")
      (node (ref "C15") (pin "2") (pinfunction "2_2") (pintype "passive"))
      (node (ref "X2") (pin "3") (pinfunction "C1+_3") (pintype "input"))
    )
    (net (code "52") (name "Net-(X2-C1-)") (class "Default")
      (node (ref "C15") (pin "1") (pinfunction "1_1") (pintype "passive"))
      (node (ref "X2") (pin "4") (pinfunction "C1-_4") (pintype "input"))
    )
    (net (code "53") (name "Net-(X2-C2+)") (class "Default")
      (node (ref "C17") (pin "2") (pinfunction "2_2") (pintype "passive"))
      (node (ref "X2") (pin "1") (pinfunction "C2+_1") (pintype "input"))
    )
    (net (code "54") (name "Net-(X2-C2-)") (class "Default")
      (node (ref "C17") (pin "1") (pinfunction "1_1") (pintype "passive"))
      (node (ref "X2") (pin "2") (pinfunction "C2-_2") (pintype "input"))
    )
    (net (code "55") (name "Net-(X2-IREF)") (class "Default")
      (node (ref "R12") (pin "2") (pinfunction "2_2") (pintype "passive"))
      (node (ref "X2") (pin "13") (pinfunction "IREF_13") (pintype "bidirectional"))
    )
    (net (code "56") (name "OLED_CS") (class "Default")
      (node (ref "IC3") (pin "34") (pinfunction "GPIO22_34") (pintype "bidirectional"))
      (node (ref "X2") (pin "8") (pinfunction "~{CS}_8") (pintype "input"))
    )
    (net (code "57") (name "OLED_DC") (class "Default")
      (node (ref "IC3") (pin "36") (pinfunction "GPIO24_36") (pintype "bidirectional"))
      (node (ref "X2") (pin "10") (pinfunction "D/~{C}_10") (pintype "input"))
    )
    (net (code "58") (name "OLED_RST") (class "Default")
      (node (ref "IC3") (pin "35") (pinfunction "GPIO23_35") (pintype "bidirectional"))
      (node (ref "R14") (pin "4") (pinfunction "1_4") (pintype "passive"))
      (node (ref "X2") (pin "9") (pinfunction "~{RES}_9") (pintype "input"))
    )
    (net (code "59") (name "QSPI_CS") (class "Default")
      (node (ref "IC3") (pin "56") (pinfunction "~{QSPI_CS}_56") (pintype "bidirectional"))
      (node (ref "R11") (pin "1") (pinfunction "1_1") (pintype "passive"))
      (node (ref "R2") (pin "2") (pinfunction "2_2") (pintype "passive"))
      (node (ref "TP6") (pin "P$1") (pinfunction "P$1_P$1") (pintype "bidirectional"))
      (node (ref "U1") (pin "1") (pinfunction "SSEL_1") (pintype "bidirectional"))
    )
    (net (code "60") (name "QSPI_DATA[0]") (class "Default")
      (node (ref "IC3") (pin "53") (pinfunction "QSPI_SD0_53") (pintype "bidirectional"))
      (node (ref "U1") (pin "5") (pinfunction "MOSI_5") (pintype "bidirectional"))
    )
    (net (code "61") (name "QSPI_DATA[1]") (class "Default")
      (node (ref "IC3") (pin "55") (pinfunction "QSPI_SD1_55") (pintype "bidirectional"))
      (node (ref "U1") (pin "2") (pinfunction "MISO_2") (pintype "bidirectional"))
    )
    (net (code "62") (name "QSPI_DATA[2]") (class "Default")
      (node (ref "IC3") (pin "54") (pinfunction "QSPI_SD2_54") (pintype "bidirectional"))
      (node (ref "U1") (pin "3") (pinfunction "WP#/IO2_3") (pintype "bidirectional"))
    )
    (net (code "63") (name "QSPI_DATA[3]") (class "Default")
      (node (ref "IC3") (pin "51") (pinfunction "QSPI_SD3_51") (pintype "bidirectional"))
      (node (ref "U1") (pin "7") (pinfunction "HOLD#/IO3_7") (pintype "bidirectional"))
    )
    (net (code "64") (name "QSPI_SCK") (class "Default")
      (node (ref "IC3") (pin "52") (pinfunction "QSPI_SCLK_52") (pintype "bidirectional"))
      (node (ref "U1") (pin "6") (pinfunction "SCK_6") (pintype "bidirectional"))
    )
    (net (code "65") (name "ROTA") (class "Default")
      (node (ref "IC3") (pin "28") (pinfunction "GPIO17_28") (pintype "bidirectional"))
      (node (ref "SW1") (pin "P$A") (pinfunction "P$A_P$A") (pintype "passive"))
    )
    (net (code "66") (name "ROTB") (class "Default")
      (node (ref "IC3") (pin "29") (pinfunction "GPIO18_29") (pintype "bidirectional"))
      (node (ref "SW1") (pin "P$B") (pinfunction "P$B_P$B") (pintype "passive"))
    )
    (net (code "67") (name "SCK") (class "Default")
      (node (ref "IC3") (pin "38") (pinfunction "GPIO26/AD0_38") (pintype "bidirectional"))
      (node (ref "X2") (pin "11") (pinfunction "SCK_11") (pintype "input"))
    )
    (net (code "68") (name "SCL") (class "Default")
      (node (ref "CONN1") (pin "4") (pinfunction "SCL_4") (pintype "passive"))
      (node (ref "IC3") (pin "32") (pinfunction "GPIO21_32") (pintype "bidirectional"))
      (node (ref "R14") (pin "3") (pinfunction "1_3") (pintype "passive"))
    )
    (net (code "69") (name "SDA") (class "Default")
      (node (ref "CONN1") (pin "3") (pinfunction "SDA_3") (pintype "passive"))
      (node (ref "IC3") (pin "31") (pinfunction "GPIO20_31") (pintype "bidirectional"))
      (node (ref "R14") (pin "2") (pinfunction "1_2") (pintype "passive"))
    )
    (net (code "70") (name "SPEAKER") (class "Default")
      (node (ref "IC3") (pin "27") (pinfunction "GPIO16_27") (pintype "bidirectional"))
      (node (ref "R8") (pin "1") (pinfunction "1_1") (pintype "passive"))
    )
    (net (code "71") (name "SPKR_SD") (class "Default")
      (node (ref "IC3") (pin "17") (pinfunction "GPIO14_17") (pintype "bidirectional"))
      (node (ref "R10") (pin "1") (pinfunction "1_1") (pintype "passive"))
      (node (ref "U3") (pin "1") (pinfunction "/SD_1") (pintype "input"))
    )
    (net (code "72") (name "USBBOOT") (class "Default")
      (node (ref "D3") (pin "C") (pinfunction "C_C") (pintype "passive"))
      (node (ref "IC3") (pin "2") (pinfunction "GPIO0_2") (pintype "bidirectional"))
      (node (ref "SW1") (pin "P$1") (pinfunction "P$1_P$1") (pintype "passive"))
    )
    (net (code "73") (name "VBUS") (class "Default")
      (node (ref "PTC1") (pin "2") (pinfunction "2_2") (pintype "passive"))
      (node (ref "X1") (pin "A4B9") (pinfunction "VBUS_A4B9") (pintype "power_in"))
      (node (ref "X1") (pin "B4A9") (pinfunction "VBUS_B4A9") (pintype "power_in"))
    )
    (net (code "74") (name "VCC") (class "Default")
      (node (ref "C14") (pin "2") (pinfunction "2_2") (pintype "passive"))
      (node (ref "X2") (pin "15") (pinfunction "VCC_15") (pintype "power_in"))
    )
    (net (code "75") (name "VCOMH") (class "Default")
      (node (ref "C9") (pin "2") (pinfunction "2_2") (pintype "passive"))
      (node (ref "X2") (pin "14") (pinfunction "VCOMH_14") (pintype "power_in"))
    )
    (net (code "76") (name "unconnected-(IC3-GPIO15-Pad18)") (class "Default")
      (node (ref "IC3") (pin "18") (pinfunction "GPIO15_18") (pintype "bidirectional"))
    )
    (net (code "77") (name "unconnected-(IC3-GPIO25-Pad37)") (class "Default")
      (node (ref "IC3") (pin "37") (pinfunction "GPIO25_37") (pintype "bidirectional"))
    )
    (net (code "78") (name "unconnected-(IC3-GPIO29{slash}AD3-Pad41)") (class "Default")
      (node (ref "IC3") (pin "41") (pinfunction "GPIO29/AD3_41") (pintype "bidirectional"))
    )
    (net (code "79") (name "unconnected-(IC3-SWCLK-Pad24)") (class "Default")
      (node (ref "IC3") (pin "24") (pinfunction "SWCLK_24") (pintype "bidirectional"))
    )
    (net (code "80") (name "unconnected-(IC3-SWDIO-Pad25)") (class "Default")
      (node (ref "IC3") (pin "25") (pinfunction "SWDIO_25") (pintype "bidirectional"))
    )
    (net (code "81") (name "unconnected-(LED12-DO-Pad2-DOUT)") (class "Default")
      (node (ref "LED12") (pin "2-DOUT") (pinfunction "DO_2-DOUT") (pintype "output"))
    )
    (net (code "82") (name "unconnected-(TP1-SEW-PadP$1)") (class "Default")
      (node (ref "TP1") (pin "P$1") (pinfunction "SEW_P$1") (pintype "bidirectional"))
    )
    (net (code "83") (name "unconnected-(TP2-SEW-PadP$1)") (class "Default")
      (node (ref "TP2") (pin "P$1") (pinfunction "SEW_P$1") (pintype "bidirectional"))
    )
    (net (code "84") (name "unconnected-(TP3-SEW-PadP$1)") (class "Default")
      (node (ref "TP3") (pin "P$1") (pinfunction "SEW_P$1") (pintype "bidirectional"))
    )
    (net (code "85") (name "unconnected-(TP4-SEW-PadP$1)") (class "Default")
      (node (ref "TP4") (pin "P$1") (pinfunction "SEW_P$1") (pintype "bidirectional"))
    )
    (net (code "86") (name "unconnected-(U2-P4-Pad4)") (class "Default")
      (node (ref "U2") (pin "4") (pinfunction "P4_4") (pintype "bidirectional"))
    )
    (net (code "87") (name "unconnected-(U3-NC-Pad2)") (class "Default")
      (node (ref "U3") (pin "2") (pinfunction "NC_2") (pintype "no_connect"))
    )
    (net (code "88") (name "unconnected-(X1A-SBU1-PadA8)") (class "Default")
      (node (ref "X1") (pin "A8") (pinfunction "SBU1_A8") (pintype "bidirectional"))
    )
    (net (code "89") (name "unconnected-(X1A-SBU2-PadB8)") (class "Default")
      (node (ref "X1") (pin "B8") (pinfunction "SBU2_B8") (pintype "bidirectional"))
    )
    (net (code "90") (name "~{RESET}") (class "Default")
      (node (ref "IC3") (pin "26") (pinfunction "/RUN_26") (pintype "bidirectional"))
      (node (ref "R14") (pin "1") (pinfunction "1_1") (pintype "passive"))
      (node (ref "SW2") (pin "2") (pinfunction "S_2") (pintype "passive"))
      (node (ref "TP5") (pin "P$1") (pinfunction "P$1_P$1") (pintype "bidirectional"))
    )
  )
)
